# trashotron-neuron-v1.net
KiCad netlist of a schematic drawn in EAGLE
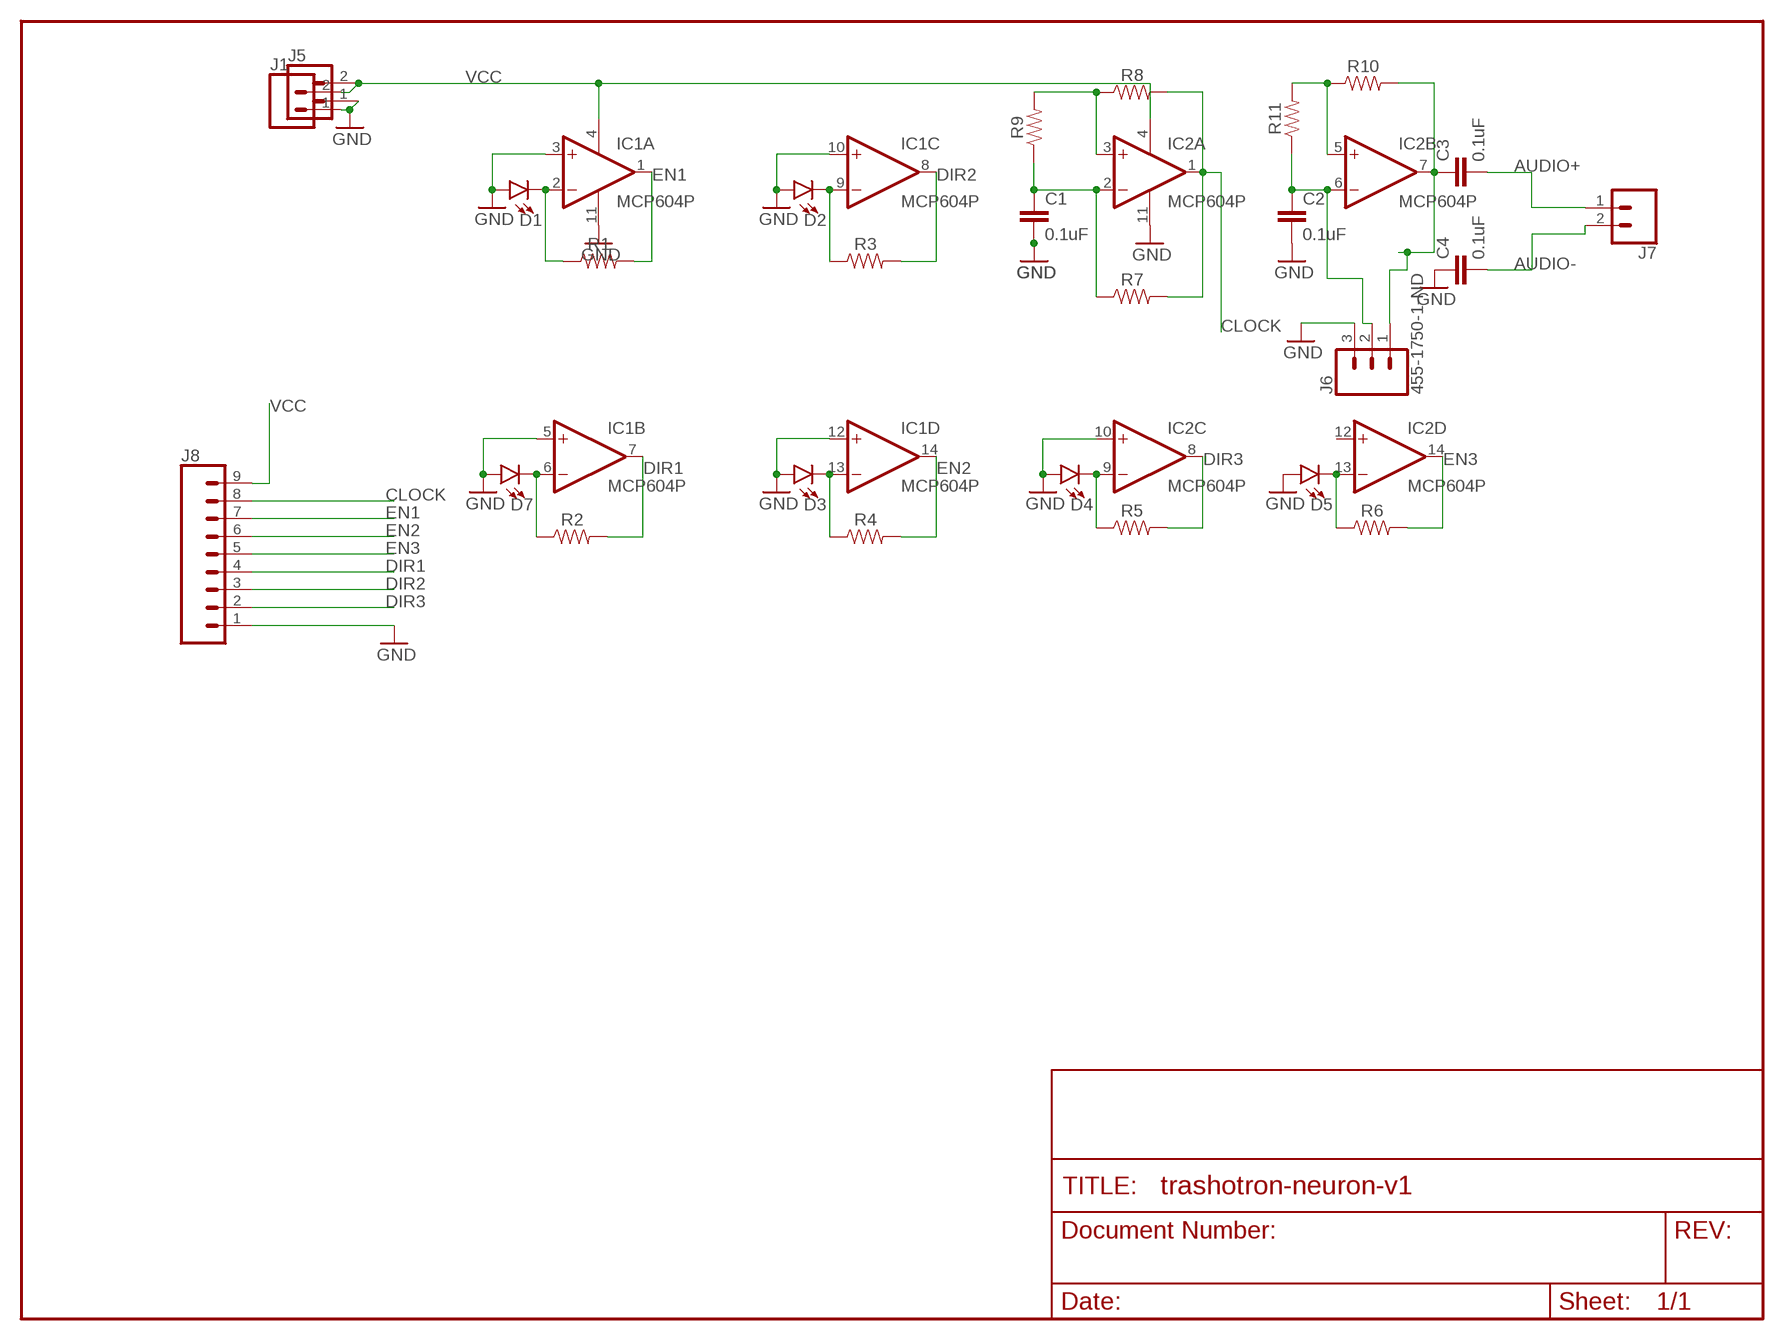
[diagram p0: schematic, sheet 1]

(export (version "E")
  (design (tool "Eeschema 10.0.6"))
  (components
    (comp (ref "C1")
      (value "0.1uF")
      (footprint "eagle-import:CAP-PTH-SMALL-KIT")
      (libsource (lib "eagle-import") (part "0.1UF-KIT-EZ-50V-20%"))
    )
    (comp (ref "C2")
      (value "0.1uF")
      (footprint "eagle-import:CAP-PTH-SMALL-KIT")
      (libsource (lib "eagle-import") (part "0.1UF-KIT-EZ-50V-20%"))
    )
    (comp (ref "C3")
      (value "0.1uF")
      (footprint "eagle-import:CAP-PTH-SMALL-KIT")
      (libsource (lib "eagle-import") (part "0.1UF-KIT-EZ-50V-20%"))
    )
    (comp (ref "C4")
      (value "0.1uF")
      (footprint "eagle-import:CAP-PTH-SMALL-KIT")
      (libsource (lib "eagle-import") (part "0.1UF-KIT-EZ-50V-20%"))
    )
    (comp (ref "D1")
      (value "LED3MM")
      (footprint "eagle-import:LED_3MM")
      (libsource (lib "eagle-import") (part "LED3MM"))
    )
    (comp (ref "D2")
      (value "LED3MM")
      (footprint "eagle-import:LED_3MM")
      (libsource (lib "eagle-import") (part "LED3MM"))
    )
    (comp (ref "D3")
      (value "LED3MM")
      (footprint "eagle-import:LED_3MM")
      (libsource (lib "eagle-import") (part "LED3MM"))
    )
    (comp (ref "D4")
      (value "LED3MM")
      (footprint "eagle-import:LED_3MM")
      (libsource (lib "eagle-import") (part "LED3MM"))
    )
    (comp (ref "D5")
      (value "LED3MM")
      (footprint "eagle-import:LED_3MM")
      (libsource (lib "eagle-import") (part "LED3MM"))
    )
    (comp (ref "D7")
      (value "LED3MM")
      (footprint "eagle-import:LED_3MM")
      (libsource (lib "eagle-import") (part "LED3MM"))
    )
    (comp (ref "IC1")
      (value "MCP604P")
      (footprint "eagle-import:DIL14")
      (libsource (lib "eagle-import") (part "MCP604P"))
    )
    (comp (ref "IC2")
      (value "MCP604P")
      (footprint "eagle-import:DIL14")
      (libsource (lib "eagle-import") (part "MCP604P"))
    )
    (comp (ref "J1")
      (value "CONN_02")
      (footprint "eagle-import:1X02")
      (libsource (lib "eagle-import") (part "CONN_02"))
    )
    (comp (ref "J5")
      (value "CONN_02")
      (footprint "eagle-import:1X02")
      (libsource (lib "eagle-import") (part "CONN_02"))
    )
    (comp (ref "J6")
      (value "455-1750-1-ND")
      (footprint "eagle-import:1X03")
      (libsource (lib "eagle-import") (part "CONN_03"))
    )
    (comp (ref "J7")
      (value "CONN_02")
      (footprint "eagle-import:1X02")
      (libsource (lib "eagle-import") (part "CONN_02"))
    )
    (comp (ref "J8")
      (value "CONN_09")
      (footprint "eagle-import:1X09")
      (libsource (lib "eagle-import") (part "CONN_09"))
    )
    (comp (ref "R1")
      (value "RESISTORAXIAL-0.3")
      (footprint "eagle-import:AXIAL-0.3")
      (libsource (lib "eagle-import") (part "RESISTORAXIAL-0.3"))
    )
    (comp (ref "R2")
      (value "RESISTORAXIAL-0.3")
      (footprint "eagle-import:AXIAL-0.3")
      (libsource (lib "eagle-import") (part "RESISTORAXIAL-0.3"))
    )
    (comp (ref "R3")
      (value "RESISTORAXIAL-0.3")
      (footprint "eagle-import:AXIAL-0.3")
      (libsource (lib "eagle-import") (part "RESISTORAXIAL-0.3"))
    )
    (comp (ref "R4")
      (value "RESISTORAXIAL-0.3")
      (footprint "eagle-import:AXIAL-0.3")
      (libsource (lib "eagle-import") (part "RESISTORAXIAL-0.3"))
    )
    (comp (ref "R5")
      (value "RESISTORAXIAL-0.3")
      (footprint "eagle-import:AXIAL-0.3")
      (libsource (lib "eagle-import") (part "RESISTORAXIAL-0.3"))
    )
    (comp (ref "R6")
      (value "RESISTORAXIAL-0.3")
      (footprint "eagle-import:AXIAL-0.3")
      (libsource (lib "eagle-import") (part "RESISTORAXIAL-0.3"))
    )
    (comp (ref "R7")
      (value "RESISTORAXIAL-0.3")
      (footprint "eagle-import:AXIAL-0.3")
      (libsource (lib "eagle-import") (part "RESISTORAXIAL-0.3"))
    )
    (comp (ref "R8")
      (value "RESISTORAXIAL-0.3")
      (footprint "eagle-import:AXIAL-0.3")
      (libsource (lib "eagle-import") (part "RESISTORAXIAL-0.3"))
    )
    (comp (ref "R9")
      (value "RESISTORAXIAL-0.3")
      (footprint "eagle-import:AXIAL-0.3")
      (libsource (lib "eagle-import") (part "RESISTORAXIAL-0.3"))
    )
    (comp (ref "R10")
      (value "RESISTORAXIAL-0.3")
      (footprint "eagle-import:AXIAL-0.3")
      (libsource (lib "eagle-import") (part "RESISTORAXIAL-0.3"))
    )
    (comp (ref "R11")
      (value "RESISTORAXIAL-0.3")
      (footprint "eagle-import:AXIAL-0.3")
      (libsource (lib "eagle-import") (part "RESISTORAXIAL-0.3"))
    )
  )
  (nets
    (net (code "1") (name "/AUDIO+") (class "Default")
      (node (ref "C3") (pin "2") (pinfunction "2_2") (pintype "passive"))
      (node (ref "J7") (pin "1") (pinfunction "1_1") (pintype "passive"))
    )
    (net (code "2") (name "/AUDIO-") (class "Default")
      (node (ref "C4") (pin "2") (pinfunction "2_2") (pintype "passive"))
      (node (ref "J7") (pin "2") (pinfunction "2_2") (pintype "passive"))
    )
    (net (code "3") (name "/CLOCK") (class "Default")
      (node (ref "IC2") (pin "1") (pinfunction "OUT_1") (pintype "output"))
      (node (ref "J8") (pin "8") (pinfunction "8_8") (pintype "passive"))
      (node (ref "R7") (pin "P$2") (pinfunction "2_P$2") (pintype "passive"))
      (node (ref "R8") (pin "P$2") (pinfunction "2_P$2") (pintype "passive"))
    )
    (net (code "4") (name "/DIR1") (class "Default")
      (node (ref "IC1") (pin "7") (pinfunction "OUT_7") (pintype "output"))
      (node (ref "J8") (pin "4") (pinfunction "4_4") (pintype "passive"))
      (node (ref "R2") (pin "P$2") (pinfunction "2_P$2") (pintype "passive"))
    )
    (net (code "5") (name "/DIR2") (class "Default")
      (node (ref "IC1") (pin "8") (pinfunction "OUT_8") (pintype "output"))
      (node (ref "J8") (pin "3") (pinfunction "3_3") (pintype "passive"))
      (node (ref "R3") (pin "P$2") (pinfunction "2_P$2") (pintype "passive"))
    )
    (net (code "6") (name "/DIR3") (class "Default")
      (node (ref "IC2") (pin "8") (pinfunction "OUT_8") (pintype "output"))
      (node (ref "J8") (pin "2") (pinfunction "2_2") (pintype "passive"))
      (node (ref "R5") (pin "P$2") (pinfunction "2_P$2") (pintype "passive"))
    )
    (net (code "7") (name "/EN1") (class "Default")
      (node (ref "IC1") (pin "1") (pinfunction "OUT_1") (pintype "output"))
      (node (ref "J8") (pin "7") (pinfunction "7_7") (pintype "passive"))
      (node (ref "R1") (pin "P$2") (pinfunction "2_P$2") (pintype "passive"))
    )
    (net (code "8") (name "/EN2") (class "Default")
      (node (ref "IC1") (pin "14") (pinfunction "OUT_14") (pintype "output"))
      (node (ref "J8") (pin "6") (pinfunction "6_6") (pintype "passive"))
      (node (ref "R4") (pin "P$2") (pinfunction "2_P$2") (pintype "passive"))
    )
    (net (code "9") (name "/EN3") (class "Default")
      (node (ref "IC2") (pin "14") (pinfunction "OUT_14") (pintype "output"))
      (node (ref "J8") (pin "5") (pinfunction "5_5") (pintype "passive"))
      (node (ref "R6") (pin "P$2") (pinfunction "2_P$2") (pintype "passive"))
    )
    (net (code "10") (name "/VCC") (class "Default")
      (node (ref "IC1") (pin "4") (pinfunction "V+_4") (pintype "power_in"))
      (node (ref "IC2") (pin "4") (pinfunction "V+_4") (pintype "power_in"))
      (node (ref "J1") (pin "2") (pinfunction "2_2") (pintype "passive"))
      (node (ref "J5") (pin "2") (pinfunction "2_2") (pintype "passive"))
      (node (ref "J8") (pin "9") (pinfunction "9_9") (pintype "passive"))
    )
    (net (code "11") (name "GND") (class "Default")
      (node (ref "C1") (pin "2") (pinfunction "2_2") (pintype "passive"))
      (node (ref "C2") (pin "2") (pinfunction "2_2") (pintype "passive"))
      (node (ref "C4") (pin "1") (pinfunction "1_1") (pintype "passive"))
      (node (ref "D1") (pin "A") (pinfunction "A_A") (pintype "passive"))
      (node (ref "D2") (pin "A") (pinfunction "A_A") (pintype "passive"))
      (node (ref "D3") (pin "A") (pinfunction "A_A") (pintype "passive"))
      (node (ref "D4") (pin "A") (pinfunction "A_A") (pintype "passive"))
      (node (ref "D5") (pin "A") (pinfunction "A_A") (pintype "passive"))
      (node (ref "D7") (pin "A") (pinfunction "A_A") (pintype "passive"))
      (node (ref "IC1") (pin "10") (pinfunction "+IN_10") (pintype "input"))
      (node (ref "IC1") (pin "11") (pinfunction "V-_11") (pintype "power_in"))
      (node (ref "IC1") (pin "12") (pinfunction "+IN_12") (pintype "input"))
      (node (ref "IC1") (pin "3") (pinfunction "+IN_3") (pintype "input"))
      (node (ref "IC1") (pin "5") (pinfunction "+IN_5") (pintype "input"))
      (node (ref "IC2") (pin "10") (pinfunction "+IN_10") (pintype "input"))
      (node (ref "IC2") (pin "11") (pinfunction "V-_11") (pintype "power_in"))
      (node (ref "J1") (pin "1") (pinfunction "1_1") (pintype "passive"))
      (node (ref "J5") (pin "1") (pinfunction "1_1") (pintype "passive"))
      (node (ref "J6") (pin "3") (pinfunction "3_3") (pintype "passive"))
      (node (ref "J8") (pin "1") (pinfunction "1_1") (pintype "passive"))
    )
    (net (code "12") (name "Net-(D1-C)") (class "Default")
      (node (ref "D1") (pin "K") (pinfunction "C_K") (pintype "passive"))
      (node (ref "IC1") (pin "2") (pinfunction "-IN_2") (pintype "input"))
      (node (ref "R1") (pin "P$1") (pinfunction "1_P$1") (pintype "passive"))
    )
    (net (code "13") (name "Net-(D2-C)") (class "Default")
      (node (ref "D2") (pin "K") (pinfunction "C_K") (pintype "passive"))
      (node (ref "IC1") (pin "9") (pinfunction "-IN_9") (pintype "input"))
      (node (ref "R3") (pin "P$1") (pinfunction "1_P$1") (pintype "passive"))
    )
    (net (code "14") (name "Net-(D3-C)") (class "Default")
      (node (ref "D3") (pin "K") (pinfunction "C_K") (pintype "passive"))
      (node (ref "IC1") (pin "13") (pinfunction "-IN_13") (pintype "input"))
      (node (ref "R4") (pin "P$1") (pinfunction "1_P$1") (pintype "passive"))
    )
    (net (code "15") (name "Net-(D4-C)") (class "Default")
      (node (ref "D4") (pin "K") (pinfunction "C_K") (pintype "passive"))
      (node (ref "IC2") (pin "9") (pinfunction "-IN_9") (pintype "input"))
      (node (ref "R5") (pin "P$1") (pinfunction "1_P$1") (pintype "passive"))
    )
    (net (code "16") (name "Net-(D5-C)") (class "Default")
      (node (ref "D5") (pin "K") (pinfunction "C_K") (pintype "passive"))
      (node (ref "IC2") (pin "13") (pinfunction "-IN_13") (pintype "input"))
      (node (ref "R6") (pin "P$1") (pinfunction "1_P$1") (pintype "passive"))
    )
    (net (code "17") (name "Net-(D7-C)") (class "Default")
      (node (ref "D7") (pin "K") (pinfunction "C_K") (pintype "passive"))
      (node (ref "IC1") (pin "6") (pinfunction "-IN_6") (pintype "input"))
      (node (ref "R2") (pin "P$1") (pinfunction "1_P$1") (pintype "passive"))
    )
    (net (code "18") (name "Net-(IC2A-+IN)") (class "Default")
      (node (ref "IC2") (pin "3") (pinfunction "+IN_3") (pintype "input"))
      (node (ref "R8") (pin "P$1") (pinfunction "1_P$1") (pintype "passive"))
      (node (ref "R9") (pin "P$2") (pinfunction "2_P$2") (pintype "passive"))
    )
    (net (code "19") (name "Net-(IC2A--IN)") (class "Default")
      (node (ref "C1") (pin "1") (pinfunction "1_1") (pintype "passive"))
      (node (ref "IC2") (pin "2") (pinfunction "-IN_2") (pintype "input"))
      (node (ref "R7") (pin "P$1") (pinfunction "1_P$1") (pintype "passive"))
      (node (ref "R9") (pin "P$1") (pinfunction "1_P$1") (pintype "passive"))
    )
    (net (code "20") (name "Net-(IC2B-+IN)") (class "Default")
      (node (ref "IC2") (pin "5") (pinfunction "+IN_5") (pintype "input"))
      (node (ref "R10") (pin "P$1") (pinfunction "1_P$1") (pintype "passive"))
      (node (ref "R11") (pin "P$2") (pinfunction "2_P$2") (pintype "passive"))
    )
    (net (code "21") (name "Net-(IC2B--IN)") (class "Default")
      (node (ref "C2") (pin "1") (pinfunction "1_1") (pintype "passive"))
      (node (ref "IC2") (pin "6") (pinfunction "-IN_6") (pintype "input"))
      (node (ref "J6") (pin "2") (pinfunction "2_2") (pintype "passive"))
      (node (ref "R11") (pin "P$1") (pinfunction "1_P$1") (pintype "passive"))
    )
    (net (code "22") (name "Net-(IC2B-OUT)") (class "Default")
      (node (ref "C3") (pin "1") (pinfunction "1_1") (pintype "passive"))
      (node (ref "IC2") (pin "7") (pinfunction "OUT_7") (pintype "output"))
      (node (ref "J6") (pin "1") (pinfunction "1_1") (pintype "passive"))
      (node (ref "R10") (pin "P$2") (pinfunction "2_P$2") (pintype "passive"))
    )
    (net (code "23") (name "unconnected-(IC2D-+IN-Pad12)") (class "Default")
      (node (ref "IC2") (pin "12") (pinfunction "+IN_12") (pintype "input"))
    )
  )
)
